# PICO_Project_1.net
KiCad netlist of a schematic drawn in Altium Designer
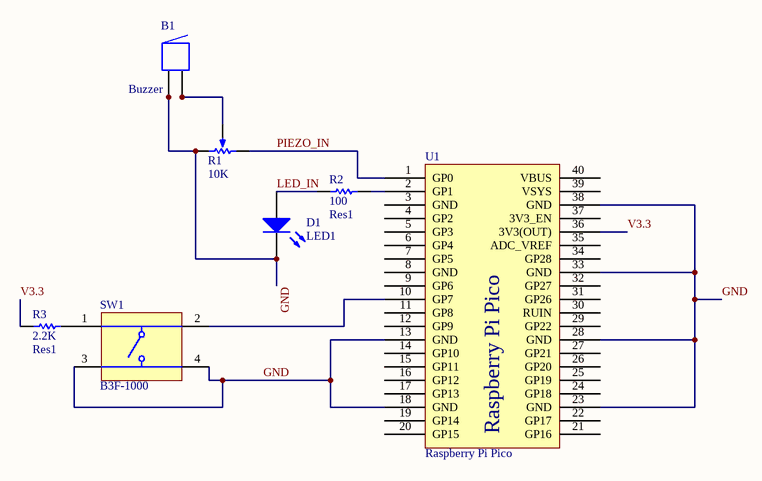
[diagram p0: PICO_Project_1.SchDoc]

(export (version "E")
  (design (tool "Eeschema 10.0.6"))
  (components
    (comp (ref "B1")
      (value "Buzzer")
      (footprint "ABSM-1574")
      (description "Magnetic Transducer Buzzer")
      (fields (field (name "PUBLISHER") "Altium Limited"))
      (libsource (lib "Miscellaneous Devices") (part "Buzzer"))
    )
    (comp (ref "D1")
      (value "LED1")
      (footprint "LED-1")
      (description "Typical RED GaAs LED")
      (fields (field (name "PUBLISHER") "Altium Limited"))
      (libsource (lib "Miscellaneous Devices") (part "LED1"))
    )
    (comp (ref "R1")
      (value "10K")
      (footprint "POT inline wide")
      (description "Potentiometer")
      (fields (field (name "Comment") "RPot_1") (field (name "PUBLISHER") "Altium Limited"))
      (libsource (lib "ECE Lib 22") (part "RPot_3"))
    )
    (comp (ref "R2")
      (value "Res1")
      (footprint "AXIAL-0.3")
      (description "Resistor")
      (fields (field (name "ALTIUM_VALUE") "100") (field (name "PUBLISHER") "Altium Limited"))
      (libsource (lib "Miscellaneous Devices") (part "Res1"))
    )
    (comp (ref "R3")
      (value "Res1")
      (footprint "AXIAL-0.3")
      (description "Resistor")
      (fields (field (name "ALTIUM_VALUE") "2.2K") (field (name "PUBLISHER") "Altium Limited"))
      (libsource (lib "Miscellaneous Devices") (part "Res1"))
    )
    (comp (ref "SW1")
      (value "B3F-1000")
      (footprint "OMRON-B3F-1000-4_V")
      (description "Tactile Switch, SPST-NO, 0.05 A, 5 to 24 V, -25 to 70 degC, 4-Pin THD, RoHS, Bulk")
      (libsource (lib "Components - 12.02.26 - 14.01") (part "CMP-1677-00002-1"))
    )
    (comp (ref "U1")
      (value "Raspberry Pi Pico")
      (footprint "Raspberry Pi Pico")
      (libsource (lib "ECE Lib 22") (part "Raspberry Pi Pico"))
    )
  )
  (nets
    (net (code "1") (name "/GND") (class "Default")
      (node (ref "B1") (pin "1") (pinfunction "1_1") (pintype "passive"))
      (node (ref "B1") (pin "1A") (pinfunction "1A_1A") (pintype "passive"))
      (node (ref "D1") (pin "2") (pinfunction "K_2") (pintype "passive"))
      (node (ref "R1") (pin "3") (pinfunction "BOT_3") (pintype "passive"))
      (node (ref "SW1") (pin "3") (pinfunction "3_3") (pintype "passive"))
      (node (ref "SW1") (pin "4") (pinfunction "4_4") (pintype "passive"))
      (node (ref "U1") (pin "13") (pinfunction "GND_13") (pintype "passive"))
      (node (ref "U1") (pin "18") (pinfunction "GND_18") (pintype "passive"))
      (node (ref "U1") (pin "23") (pinfunction "GND_23") (pintype "passive"))
      (node (ref "U1") (pin "28") (pinfunction "GND_28") (pintype "passive"))
      (node (ref "U1") (pin "33") (pinfunction "GND_33") (pintype "passive"))
      (node (ref "U1") (pin "38") (pinfunction "GND_38") (pintype "passive"))
    )
    (net (code "2") (name "/LED_IN") (class "Default")
      (node (ref "D1") (pin "1") (pinfunction "A_1") (pintype "passive"))
      (node (ref "R2") (pin "2") (pinfunction "2_2") (pintype "passive"))
    )
    (net (code "3") (name "/PIEZO_IN") (class "Default")
      (node (ref "R1") (pin "1") (pinfunction "TOP_1") (pintype "passive"))
      (node (ref "U1") (pin "1") (pinfunction "GP0_1") (pintype "passive"))
    )
    (net (code "4") (name "/V3.3") (class "Default")
      (node (ref "R3") (pin "2") (pinfunction "2_2") (pintype "passive"))
      (node (ref "U1") (pin "36") (pinfunction "3V3(OUT)_36") (pintype "passive"))
    )
    (net (code "5") (name "Net-(R1-TAP)") (class "Default")
      (node (ref "B1") (pin "2") (pinfunction "2_2") (pintype "passive"))
      (node (ref "B1") (pin "2A") (pinfunction "2A_2A") (pintype "passive"))
      (node (ref "R1") (pin "2") (pinfunction "TAP_2") (pintype "passive"))
    )
    (net (code "6") (name "Net-(R3-Pad1)") (class "Default")
      (node (ref "R3") (pin "1") (pinfunction "1_1") (pintype "passive"))
      (node (ref "SW1") (pin "1") (pinfunction "1_1") (pintype "passive"))
    )
    (net (code "7") (name "Net-(U1-GP1)") (class "Default")
      (node (ref "R2") (pin "1") (pinfunction "1_1") (pintype "passive"))
      (node (ref "U1") (pin "2") (pinfunction "GP1_2") (pintype "passive"))
    )
    (net (code "8") (name "Net-(U1-GP7)") (class "Default")
      (node (ref "SW1") (pin "2") (pinfunction "2_2") (pintype "passive"))
      (node (ref "U1") (pin "10") (pinfunction "GP7_10") (pintype "passive"))
    )
    (net (code "9") (name "unconnected-(U1-3V3_EN-Pad37)") (class "Default")
      (node (ref "U1") (pin "37") (pinfunction "3V3_EN_37") (pintype "passive"))
    )
    (net (code "10") (name "unconnected-(U1-ADC_VREF-Pad35)") (class "Default")
      (node (ref "U1") (pin "35") (pinfunction "ADC_VREF_35") (pintype "passive"))
    )
    (net (code "11") (name "unconnected-(U1-GND-Pad3)") (class "Default")
      (node (ref "U1") (pin "3") (pinfunction "GND_3") (pintype "passive"))
    )
    (net (code "12") (name "unconnected-(U1-GND-Pad8)") (class "Default")
      (node (ref "U1") (pin "8") (pinfunction "GND_8") (pintype "passive"))
    )
    (net (code "13") (name "unconnected-(U1-GP2-Pad4)") (class "Default")
      (node (ref "U1") (pin "4") (pinfunction "GP2_4") (pintype "passive"))
    )
    (net (code "14") (name "unconnected-(U1-GP3-Pad5)") (class "Default")
      (node (ref "U1") (pin "5") (pinfunction "GP3_5") (pintype "passive"))
    )
    (net (code "15") (name "unconnected-(U1-GP4-Pad6)") (class "Default")
      (node (ref "U1") (pin "6") (pinfunction "GP4_6") (pintype "passive"))
    )
    (net (code "16") (name "unconnected-(U1-GP5-Pad7)") (class "Default")
      (node (ref "U1") (pin "7") (pinfunction "GP5_7") (pintype "passive"))
    )
    (net (code "17") (name "unconnected-(U1-GP6-Pad9)") (class "Default")
      (node (ref "U1") (pin "9") (pinfunction "GP6_9") (pintype "passive"))
    )
    (net (code "18") (name "unconnected-(U1-GP8-Pad11)") (class "Default")
      (node (ref "U1") (pin "11") (pinfunction "GP8_11") (pintype "passive"))
    )
    (net (code "19") (name "unconnected-(U1-GP9-Pad12)") (class "Default")
      (node (ref "U1") (pin "12") (pinfunction "GP9_12") (pintype "passive"))
    )
    (net (code "20") (name "unconnected-(U1-GP10-Pad14)") (class "Default")
      (node (ref "U1") (pin "14") (pinfunction "GP10_14") (pintype "passive"))
    )
    (net (code "21") (name "unconnected-(U1-GP11-Pad15)") (class "Default")
      (node (ref "U1") (pin "15") (pinfunction "GP11_15") (pintype "passive"))
    )
    (net (code "22") (name "unconnected-(U1-GP12-Pad16)") (class "Default")
      (node (ref "U1") (pin "16") (pinfunction "GP12_16") (pintype "passive"))
    )
    (net (code "23") (name "unconnected-(U1-GP13-Pad17)") (class "Default")
      (node (ref "U1") (pin "17") (pinfunction "GP13_17") (pintype "passive"))
    )
    (net (code "24") (name "unconnected-(U1-GP14-Pad19)") (class "Default")
      (node (ref "U1") (pin "19") (pinfunction "GP14_19") (pintype "passive"))
    )
    (net (code "25") (name "unconnected-(U1-GP15-Pad20)") (class "Default")
      (node (ref "U1") (pin "20") (pinfunction "GP15_20") (pintype "passive"))
    )
    (net (code "26") (name "unconnected-(U1-GP16-Pad21)") (class "Default")
      (node (ref "U1") (pin "21") (pinfunction "GP16_21") (pintype "passive"))
    )
    (net (code "27") (name "unconnected-(U1-GP17-Pad22)") (class "Default")
      (node (ref "U1") (pin "22") (pinfunction "GP17_22") (pintype "passive"))
    )
    (net (code "28") (name "unconnected-(U1-GP18-Pad24)") (class "Default")
      (node (ref "U1") (pin "24") (pinfunction "GP18_24") (pintype "passive"))
    )
    (net (code "29") (name "unconnected-(U1-GP19-Pad25)") (class "Default")
      (node (ref "U1") (pin "25") (pinfunction "GP19_25") (pintype "passive"))
    )
    (net (code "30") (name "unconnected-(U1-GP20-Pad26)") (class "Default")
      (node (ref "U1") (pin "26") (pinfunction "GP20_26") (pintype "passive"))
    )
    (net (code "31") (name "unconnected-(U1-GP21-Pad27)") (class "Default")
      (node (ref "U1") (pin "27") (pinfunction "GP21_27") (pintype "passive"))
    )
    (net (code "32") (name "unconnected-(U1-GP22-Pad29)") (class "Default")
      (node (ref "U1") (pin "29") (pinfunction "GP22_29") (pintype "passive"))
    )
    (net (code "33") (name "unconnected-(U1-GP26-Pad31)") (class "Default")
      (node (ref "U1") (pin "31") (pinfunction "GP26_31") (pintype "passive"))
    )
    (net (code "34") (name "unconnected-(U1-GP27-Pad32)") (class "Default")
      (node (ref "U1") (pin "32") (pinfunction "GP27_32") (pintype "passive"))
    )
    (net (code "35") (name "unconnected-(U1-GP28-Pad34)") (class "Default")
      (node (ref "U1") (pin "34") (pinfunction "GP28_34") (pintype "passive"))
    )
    (net (code "36") (name "unconnected-(U1-RUIN-Pad30)") (class "Default")
      (node (ref "U1") (pin "30") (pinfunction "RUIN_30") (pintype "passive"))
    )
    (net (code "37") (name "unconnected-(U1-VBUS-Pad40)") (class "Default")
      (node (ref "U1") (pin "40") (pinfunction "VBUS_40") (pintype "passive"))
    )
    (net (code "38") (name "unconnected-(U1-VSYS-Pad39)") (class "Default")
      (node (ref "U1") (pin "39") (pinfunction "VSYS_39") (pintype "passive"))
    )
  )
)
